# Wacky_Hat_Schematic.net
KiCad netlist of a schematic drawn in Altium Designer
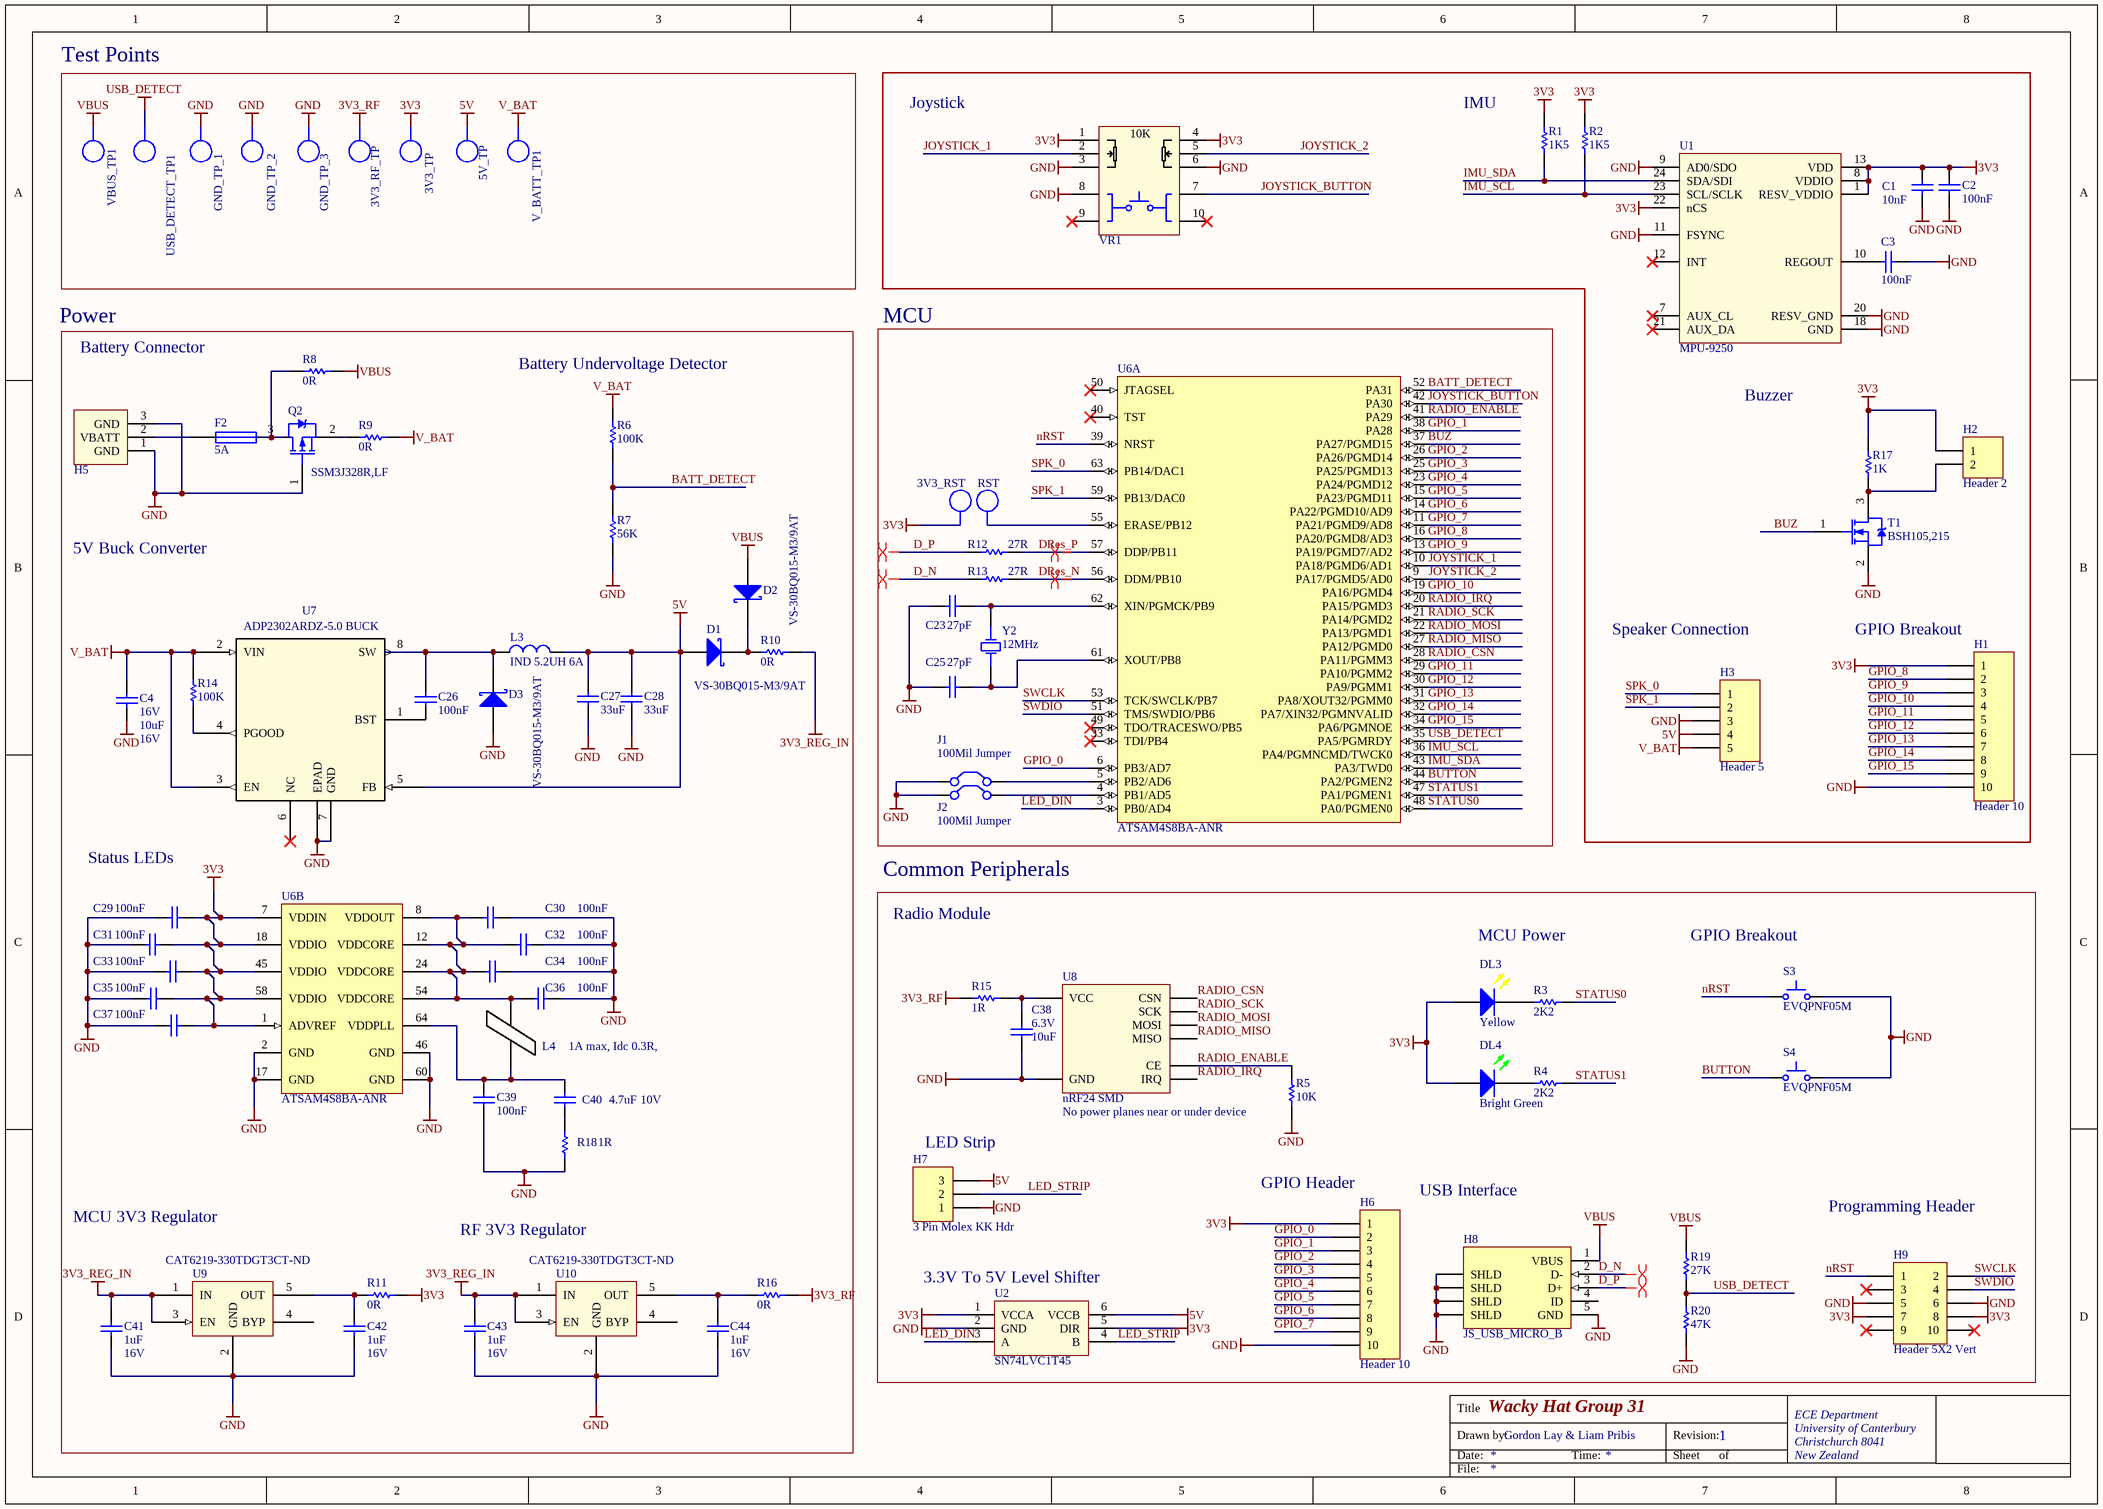
[diagram p0: Wacky Hat Schematic.SchDoc]

(export (version "E")
  (design (tool "Eeschema 10.0.6"))
  (components
    (comp (ref "3V3_RF_TP")
      (value "TP")
      (footprint "TP_1206")
      (description "Test-Point 3.3x1.6x2.1mm SMD")
      (fields
        (field (name "MANUFACTURER") "Harwin Inc")
        (field (name "MANUFACTURER PART NUMBER") "S1751-46R")
      )
      (libsource (lib "ECE AD19Components_19V1") (part "TP_1206"))
    )
    (comp (ref "3V3_RST")
      (value "TP")
      (footprint "TP_1206")
      (description "Test-Point 3.3x1.6x2.1mm SMD")
      (fields
        (field (name "MANUFACTURER") "Harwin Inc")
        (field (name "MANUFACTURER PART NUMBER") "S1751-46R")
      )
      (libsource (lib "ECE AD19Components_19V1") (part "TP_1206"))
    )
    (comp (ref "3V3_TP")
      (value "TP")
      (footprint "TP_1206")
      (description "Test-Point 3.3x1.6x2.1mm SMD")
      (fields
        (field (name "MANUFACTURER") "Harwin Inc")
        (field (name "MANUFACTURER PART NUMBER") "S1751-46R")
      )
      (libsource (lib "ECE AD19Components_19V1") (part "TP_1206"))
    )
    (comp (ref "5V_TP")
      (value "TP")
      (footprint "TP_1206")
      (description "Test-Point 3.3x1.6x2.1mm SMD")
      (fields
        (field (name "MANUFACTURER") "Harwin Inc")
        (field (name "MANUFACTURER PART NUMBER") "S1751-46R")
      )
      (libsource (lib "ECE AD19Components_19V1") (part "TP_1206"))
    )
    (comp (ref "C1")
      (value "10nF")
      (footprint "CAPC1608L")
      (description "CAP CER 10nF X7R +-10% 50V 0603")
      (libsource (lib "ECE AD19Components_19V1") (part "CC_10nF_0603"))
    )
    (comp (ref "C2")
      (value "100nF")
      (footprint "CAPC1608L")
      (description "CAP CER 100nF X7R +-10% 50V 0603")
      (libsource (lib "ECE AD19Components_19V1") (part "CC_100nF_0603"))
    )
    (comp (ref "C3")
      (value "100nF")
      (footprint "CAPC1608L")
      (description "CAP CER 100nF X7R +-10% 50V 0603")
      (libsource (lib "ECE AD19Components_19V1") (part "CC_100nF_0603"))
    )
    (comp (ref "C4")
      (value "10uF")
      (footprint "CAPC2012L")
      (description "CAP CER 10uF X5R 16V 0805")
      (fields
        (field (name "MANUFACTURER") "Samsung Electro-Mechanics")
        (field (name "MANUFACTURER PART NUMBER") "CL21A106KOQNNWE")
        (field (name "VOLTAGE - RATED") "16V")
        (field (name "MAX VOLTAGE") "16V")
      )
      (libsource (lib "ENCE461AD19_19V2") (part "CC_10uF_16V_0805"))
    )
    (comp (ref "C23")
      (value "27pF")
      (footprint "CAPC1608L")
      (description "CAP CER 27pF NPO/COG +-5% 50V 0603")
      (libsource (lib "ECE AD19Components_19V1") (part "CC_27pF_0603"))
    )
    (comp (ref "C25")
      (value "27pF")
      (footprint "CAPC1608L")
      (description "CAP CER 27pF NPO/COG +-5% 50V 0603")
      (libsource (lib "ECE AD19Components_19V1") (part "CC_27pF_0603"))
    )
    (comp (ref "C26")
      (value "100nF")
      (footprint "CAPC1608L")
      (description "CAP CER 100nF X7R +-10% 50V 0603")
      (libsource (lib "ECE AD19Components_19V1") (part "CC_100nF_0603"))
    )
    (comp (ref "C27")
      (value "33uF")
      (footprint "CAPC2012L")
      (description "CAP CER 33uF X5R 6V3 0805")
      (fields
        (field (name "MANUFACTURER") "TDK Corporation")
        (field (name "MANUFACTURER PART NUMBER") "C2012X5R0J336M125AC")
      )
      (libsource (lib "ENCE461AD19_19V2") (part "CC_33uF_6V3_0805"))
    )
    (comp (ref "C28")
      (value "33uF")
      (footprint "CAPC2012L")
      (description "CAP CER 33uF X5R 6V3 0805")
      (fields
        (field (name "MANUFACTURER") "TDK Corporation")
        (field (name "MANUFACTURER PART NUMBER") "C2012X5R0J336M125AC")
      )
      (libsource (lib "ENCE461AD19_19V2") (part "CC_33uF_6V3_0805"))
    )
    (comp (ref "C29")
      (value "100nF")
      (footprint "CAPC1608L")
      (description "CAP CER 100nF X7R +-10% 50V 0603")
      (libsource (lib "ECE AD19Components_19V1") (part "CC_100nF_0603"))
    )
    (comp (ref "C30")
      (value "100nF")
      (footprint "CAPC1608L")
      (description "CAP CER 100nF X7R +-10% 50V 0603")
      (libsource (lib "ECE AD19Components_19V1") (part "CC_100nF_0603"))
    )
    (comp (ref "C31")
      (value "100nF")
      (footprint "CAPC1608L")
      (description "CAP CER 100nF X7R +-10% 50V 0603")
      (libsource (lib "ECE AD19Components_19V1") (part "CC_100nF_0603"))
    )
    (comp (ref "C32")
      (value "100nF")
      (footprint "CAPC1608L")
      (description "CAP CER 100nF X7R +-10% 50V 0603")
      (libsource (lib "ECE AD19Components_19V1") (part "CC_100nF_0603"))
    )
    (comp (ref "C33")
      (value "100nF")
      (footprint "CAPC1608L")
      (description "CAP CER 100nF X7R +-10% 50V 0603")
      (libsource (lib "ECE AD19Components_19V1") (part "CC_100nF_0603"))
    )
    (comp (ref "C34")
      (value "100nF")
      (footprint "CAPC1608L")
      (description "CAP CER 100nF X7R +-10% 50V 0603")
      (libsource (lib "ECE AD19Components_19V1") (part "CC_100nF_0603"))
    )
    (comp (ref "C35")
      (value "100nF")
      (footprint "CAPC1608L")
      (description "CAP CER 100nF X7R +-10% 50V 0603")
      (libsource (lib "ECE AD19Components_19V1") (part "CC_100nF_0603"))
    )
    (comp (ref "C36")
      (value "100nF")
      (footprint "CAPC1608L")
      (description "CAP CER 100nF X7R +-10% 50V 0603")
      (libsource (lib "ECE AD19Components_19V1") (part "CC_100nF_0603"))
    )
    (comp (ref "C37")
      (value "100nF")
      (footprint "CAPC1608L")
      (description "CAP CER 100nF X7R +-10% 50V 0603")
      (libsource (lib "ECE AD19Components_19V1") (part "CC_100nF_0603"))
    )
    (comp (ref "C38")
      (value "10uF")
      (footprint "CAPC1608L")
      (description "CAP CER 10UF X5R +-20% 6V3 0603")
      (fields (field (name "VOLTAGE - RATED") "6.3V"))
      (libsource (lib "ECE AD19Components_19V1") (part "CC_10uF_0603"))
    )
    (comp (ref "C39")
      (value "100nF")
      (footprint "CAPC1608L")
      (description "CAP CER 100nF X7R +-10% 50V 0603")
      (libsource (lib "ECE AD19Components_19V1") (part "CC_100nF_0603"))
    )
    (comp (ref "C40")
      (value "4.7uF")
      (footprint "CAPC1608N")
      (description "CAP CER 4.7uF X5R +-20%  10V 0603")
      (fields (field (name "MAX VOLTAGE") "10V"))
      (libsource (lib "ECE AD19Components_19V1") (part "CC_4.7uF_0603"))
    )
    (comp (ref "C41")
      (value "1uF")
      (footprint "CAPC1608L")
      (description "CAP CER 1uF Y5V -20% +80% 16V 0603")
      (fields (field (name "MAX VOLTAGE") "16V"))
      (libsource (lib "ECE AD19Components_19V1") (part "CC_1uF_0603"))
    )
    (comp (ref "C42")
      (value "1uF")
      (footprint "CAPC1608L")
      (description "CAP CER 1uF Y5V -20% +80% 16V 0603")
      (fields (field (name "MAX VOLTAGE") "16V"))
      (libsource (lib "ECE AD19Components_19V1") (part "CC_1uF_0603"))
    )
    (comp (ref "C43")
      (value "1uF")
      (footprint "CAPC1608L")
      (description "CAP CER 1uF Y5V -20% +80% 16V 0603")
      (fields (field (name "MAX VOLTAGE") "16V"))
      (libsource (lib "ECE AD19Components_19V1") (part "CC_1uF_0603"))
    )
    (comp (ref "C44")
      (value "1uF")
      (footprint "CAPC1608L")
      (description "CAP CER 1uF Y5V -20% +80% 16V 0603")
      (fields (field (name "MAX VOLTAGE") "16V"))
      (libsource (lib "ECE AD19Components_19V1") (part "CC_1uF_0603"))
    )
    (comp (ref "D1")
      (value "VS-30BQ015-M3/9AT")
      (footprint "SMC")
      (description "DIODE, SCHOTTKY, 3A, 15V, DO-214AB / SMC")
      (fields (field (name "MANUFACTURER") "Vishay Semiconductors"))
      (libsource (lib "ECE AD19Components_19V1") (part "DS_VS-30BQ015-M3"))
    )
    (comp (ref "D2")
      (value "VS-30BQ015-M3/9AT")
      (footprint "SMC")
      (description "DIODE, SCHOTTKY, 3A, 15V, DO-214AB / SMC")
      (fields (field (name "MANUFACTURER") "Vishay Semiconductors"))
      (libsource (lib "ECE AD19Components_19V1") (part "DS_VS-30BQ015-M3"))
    )
    (comp (ref "D3")
      (value "VS-30BQ015-M3/9AT")
      (footprint "SMC")
      (description "DIODE, SCHOTTKY, 3A, 15V, DO-214AB / SMC")
      (fields (field (name "MANUFACTURER") "Vishay Semiconductors"))
      (libsource (lib "ECE AD19Components_19V1") (part "DS_VS-30BQ015-M3"))
    )
    (comp (ref "DL3")
      (value "Yellow")
      (footprint "WL-SMCW0603")
      (description "LED Yellow 120mcd 0603 SMD")
      (fields
        (field (name "MANUFACTURER") "WURTH ELEKTRONIK")
        (field (name "MANUFACTURER PART NUMBER") "150060YS75000")
        (field (name "LED COLOUR") "Yellow")
      )
      (libsource (lib "ECE AD19Components_19V1") (part "DL_150060YS75000"))
    )
    (comp (ref "DL4")
      (value "Bright Green")
      (footprint "WL-SMCW0603")
      (description "LED Bright Green 40mcd 0603 SMD")
      (fields
        (field (name "MANUFACTURER") "WURTH ELEKTRONIK")
        (field (name "MANUFACTURER PART NUMBER") "150060VS75000")
        (field (name "LED COLOUR") "Bright Green")
      )
      (libsource (lib "ECE AD19Components_19V1") (part "DL_150060VS75000"))
    )
    (comp (ref "F2")
      (value "5A")
      (footprint "RESC3216N")
      (description "Fuse 5.0A Fast Acting 1206 SMD")
      (fields (field (name "MANUFACTURER PART NUMBER") "C1F5") (field (name "MANUFACTURER") "Bel TRP"))
      (libsource (lib "ECE AD19Components_19V1") (part "FS_Fuse_5.0A"))
    )
    (comp (ref "GND_TP_1")
      (value "TP")
      (footprint "TP_1206")
      (description "Test-Point 3.3x1.6x2.1mm SMD")
      (fields
        (field (name "MANUFACTURER") "Harwin Inc")
        (field (name "MANUFACTURER PART NUMBER") "S1751-46R")
      )
      (libsource (lib "ECE AD19Components_19V1") (part "TP_1206"))
    )
    (comp (ref "GND_TP_2")
      (value "TP")
      (footprint "TP_1206")
      (description "Test-Point 3.3x1.6x2.1mm SMD")
      (fields
        (field (name "MANUFACTURER") "Harwin Inc")
        (field (name "MANUFACTURER PART NUMBER") "S1751-46R")
      )
      (libsource (lib "ECE AD19Components_19V1") (part "TP_1206"))
    )
    (comp (ref "GND_TP_3")
      (value "TP")
      (footprint "TP_1206")
      (description "Test-Point 3.3x1.6x2.1mm SMD")
      (fields
        (field (name "MANUFACTURER") "Harwin Inc")
        (field (name "MANUFACTURER PART NUMBER") "S1751-46R")
      )
      (libsource (lib "ECE AD19Components_19V1") (part "TP_1206"))
    )
    (comp (ref "H1")
      (value "Header 10")
      (footprint "HDR1X10")
      (description "Header, 10-Pin")
      (fields (field (name "PUBLISHER") "Altium Limited"))
      (libsource (lib "Miscellaneous Connectors") (part "Header 10"))
    )
    (comp (ref "H2")
      (value "Header 2")
      (footprint "HDR1X2")
      (description "Header, 2-Pin")
      (fields (field (name "PUBLISHER") "Altium Limited"))
      (libsource (lib "Miscellaneous Connectors") (part "Header 2"))
    )
    (comp (ref "H3")
      (value "Header 5")
      (footprint "HDR1X5")
      (description "Header, 5-Pin")
      (fields (field (name "PUBLISHER") "Altium Limited"))
      (libsource (lib "Miscellaneous Connectors") (part "Header 5"))
    )
    (comp (ref "H5")
      (value "Battery_HEADER_3pin")
      (footprint "BATT_HEADER_3POS")
      (description "3Pin Header 2.54mm spacing")
      (libsource (lib "ENCE461AD19_19V2") (part "Battery_HEADER_3pin"))
    )
    (comp (ref "H6")
      (value "Header 10")
      (footprint "HDR1X10")
      (description "Header, 10-Pin")
      (fields (field (name "PUBLISHER") "Altium Limited"))
      (libsource (lib "Miscellaneous Connectors") (part "Header 10"))
    )
    (comp (ref "H7")
      (value "3 Pin Molex KK Hdr")
      (footprint "MOLEX_KK_3_HDR")
      (description "CONN HEADER 3POS 2.54mm VERT_Thru Hole")
      (fields (field (name "MANUFACTURER") "Molex"))
      (libsource (lib "ECE AD19Components_19V1") (part "JA_MOLEX_KK_3POS"))
    )
    (comp (ref "H8")
      (value "JS_USB_MICRO_B")
      (footprint "FCI_USB_10118194-0001LF")
      (description "CONN USB MICRO B RECPT SMT R/A")
      (fields (field (name "MANUFACTURER") "FCI") (field (name "MANUFACTURER PART NUMBER") "10118194-0001LF"))
      (libsource (lib "ECE AD19Components_19V1") (part "JS_USB_MICRO_B_SMT"))
    )
    (comp (ref "H9")
      (value "Header 5X2 Vert")
      (footprint "IDC2.54-V10D")
      (description "IDC Header, 2,54mm, 10-Pin, Vert")
      (libsource (lib "ECE AD19Components_19V1") (part "JA_HDR_IDC_5X2_VERT"))
    )
    (comp (ref "J1")
      (value "100Mil Jumper")
      (footprint "JMP2.54")
      (description "2.54mm Jumper Thru Hole")
      (libsource (lib "ECE AD19Components_19V1") (part "TP_JUMPER"))
    )
    (comp (ref "J2")
      (value "100Mil Jumper")
      (footprint "JMP2.54")
      (description "2.54mm Jumper Thru Hole")
      (libsource (lib "ECE AD19Components_19V1") (part "TP_JUMPER"))
    )
    (comp (ref "L3")
      (value "IND 5.2UH 6A")
      (footprint "INDUCTOR5u2")
      (description "FIXED IND 5.2UH 6A 22 MOHM SMD")
      (fields
        (field (name "MANUFACTURER") "Sumida America Components Inc.")
        (field (name "MANUFACTURER PART NUMBER") "CDRH104RNP-5R2NC")
      )
      (libsource (lib "ENCE461AD19_19V2") (part "CDRH104RNP-5R2NC"))
    )
    (comp (ref "L4")
      (value "1A max, Idc 0.3R,")
      (footprint "INDC3216L")
      (description "Ferrite Bead, Rdc 0.3R, Z100MHZ 600R, Imax 1A, SMD 1206")
      (fields
        (field (name "MANUFACTURER") "FAIR-RITE")
        (field (name "MANUFACTURER PART NUMBER") "2512066017Y1")
      )
      (libsource (lib "ECE AD19Components_19V1") (part "IN_Ferrite-Bead"))
    )
    (comp (ref "Q2")
      (value "SSM3J328R,LF")
      (footprint "SOT23_L")
      (description "MOSFET P-CH 20V 6A SOT23-3")
      (fields
        (field (name "MANUFACTURER") "Toshiba")
        (field (name "MANUFACTURER PART NUMBER") "SSM3J328R,LF")
      )
      (libsource (lib "ECE AD19Components_19V1") (part "TM_SSM3J328R"))
    )
    (comp (ref "R1")
      (value "1K5")
      (footprint "RESC1608L")
      (description "RES 1.5K OHM 1/10W 5% 0603 SMD")
      (libsource (lib "ECE AD19Components_19V1") (part "RS_1K5"))
    )
    (comp (ref "R2")
      (value "1K5")
      (footprint "RESC1608L")
      (description "RES 1.5K OHM 1/10W 5% 0603 SMD")
      (libsource (lib "ECE AD19Components_19V1") (part "RS_1K5"))
    )
    (comp (ref "R3")
      (value "2K2")
      (footprint "RESC1608L")
      (description "RES 2.2K OHM 1/10W 5% 0603 SMD")
      (libsource (lib "ECE AD19Components_19V1") (part "RS_2K2"))
    )
    (comp (ref "R4")
      (value "2K2")
      (footprint "RESC1608L")
      (description "RES 2.2K OHM 1/10W 5% 0603 SMD")
      (libsource (lib "ECE AD19Components_19V1") (part "RS_2K2"))
    )
    (comp (ref "R5")
      (value "10K")
      (footprint "RESC1608L")
      (description "RES 10.0K OHM 1/10W 5% 0603 SMD")
      (libsource (lib "ECE AD19Components_19V1") (part "RS_10K"))
    )
    (comp (ref "R6")
      (value "100K")
      (footprint "RESC1608L")
      (description "RES 100K OHM 1/10W 5% 0603 SMD")
      (libsource (lib "ECE AD19Components_19V1") (part "RS_100K"))
    )
    (comp (ref "R7")
      (value "56K")
      (footprint "RESC1608L")
      (description "RES 56.0K OHM 1/10W 5% 0603 SMD")
      (libsource (lib "ECE AD19Components_19V1") (part "RS_56K"))
    )
    (comp (ref "R8")
      (value "0R")
      (footprint "RESC1608L")
      (description "RES 0.0 OHM 1/10W 5% 0603 SMD")
      (libsource (lib "ECE AD19Components_19V1") (part "RS_0R0"))
    )
    (comp (ref "R9")
      (value "0R")
      (footprint "RESC1608L")
      (description "RES 0.0 OHM 1/10W 5% 0603 SMD")
      (libsource (lib "ECE AD19Components_19V1") (part "RS_0R0"))
    )
    (comp (ref "R10")
      (value "0R")
      (footprint "RESC1608L")
      (description "RES 0.0 OHM 1/10W 5% 0603 SMD")
      (libsource (lib "ECE AD19Components_19V1") (part "RS_0R0"))
    )
    (comp (ref "R11")
      (value "0R")
      (footprint "RESC1608L")
      (description "RES 0.0 OHM 1/10W 5% 0603 SMD")
      (libsource (lib "ECE AD19Components_19V1") (part "RS_0R0"))
    )
    (comp (ref "R12")
      (value "27R")
      (footprint "RESC1608L")
      (description "RES 27 OHM 1/10W 5% 0603 SMD")
      (libsource (lib "ECE AD19Components_19V1") (part "RS_27R"))
    )
    (comp (ref "R13")
      (value "27R")
      (footprint "RESC1608L")
      (description "RES 27 OHM 1/10W 5% 0603 SMD")
      (libsource (lib "ECE AD19Components_19V1") (part "RS_27R"))
    )
    (comp (ref "R14")
      (value "100K")
      (footprint "RESC1608L")
      (description "RES 100K OHM 1/10W 5% 0603 SMD")
      (libsource (lib "ECE AD19Components_19V1") (part "RS_100K"))
    )
    (comp (ref "R15")
      (value "1R")
      (footprint "RESC3216L")
      (description "RES 1R OHM 1/4W 5% 1206 SMD")
      (libsource (lib "ECE AD19Components_19V1") (part "RT_1R"))
    )
    (comp (ref "R16")
      (value "0R")
      (footprint "RESC1608L")
      (description "RES 0.0 OHM 1/10W 5% 0603 SMD")
      (libsource (lib "ECE AD19Components_19V1") (part "RS_0R0"))
    )
    (comp (ref "R17")
      (value "1K")
      (footprint "RESC1608L")
      (description "RES 1.0K OHM 1/10W 5% 0603 SMD")
      (libsource (lib "ECE AD19Components_19V1") (part "RS_1K"))
    )
    (comp (ref "R18")
      (value "1R")
      (footprint "RESC3216L")
      (description "RES 1R OHM 1/4W 5% 1206 SMD")
      (libsource (lib "ECE AD19Components_19V1") (part "RT_1R"))
    )
    (comp (ref "R19")
      (value "27K")
      (footprint "RESC1608L")
      (description "RES 27K OHM 1/10W 5% 0603 SMD")
      (libsource (lib "ECE AD19Components_19V1") (part "RS_27K"))
    )
    (comp (ref "R20")
      (value "47K")
      (footprint "RESC1608L")
      (description "RES 47.0K OHM 1/10W 5% 0603 SMD")
      (libsource (lib "ECE AD19Components_19V1") (part "RS_47K"))
    )
    (comp (ref "RST")
      (value "TP")
      (footprint "TP_1206")
      (description "Test-Point 3.3x1.6x2.1mm SMD")
      (fields
        (field (name "MANUFACTURER") "Harwin Inc")
        (field (name "MANUFACTURER PART NUMBER") "S1751-46R")
      )
      (libsource (lib "ECE AD19Components_19V1") (part "TP_1206"))
    )
    (comp (ref "S3")
      (value "EVQPNF05M")
      (footprint "EVQPNF05M")
      (description "Panasonic 6 x 3.5mm SMD Light Touch Switch Type SMD")
      (fields (field (name "MANUFACTURER") "Panasonic"))
      (libsource (lib "ECE AD19Components_19V1") (part "WS_EVQPNF05M"))
    )
    (comp (ref "S4")
      (value "EVQPNF05M")
      (footprint "EVQPNF05M")
      (description "Panasonic 6 x 3.5mm SMD Light Touch Switch Type SMD")
      (fields (field (name "MANUFACTURER") "Panasonic"))
      (libsource (lib "ECE AD19Components_19V1") (part "WS_EVQPNF05M"))
    )
    (comp (ref "T1")
      (value "BSH105,215")
      (footprint "SOT23_L")
      (description "MOSFET N-CH 20V 1.05A SOT-23")
      (fields
        (field (name "MANUFACTURER") "NXP Semiconductors")
        (field (name "MANUFACTURER PART NUMBER") "BSH105,215")
      )
      (libsource (lib "ECE AD19Components_19V1") (part "TM_BSH105"))
    )
    (comp (ref "U1")
      (value "MPU-9250")
      (footprint "Quad24")
      (description "9 axis IMU")
      (libsource (lib "ENCE461AD19_19V2") (part "MPU-9250"))
    )
    (comp (ref "U2")
      (value "SN74LVC1T45")
      (footprint "SOT23-6_N")
      (description "1.8V - 5V level converter")
      (libsource (lib "ENCE461_extras_2020") (part "SN74LVC1T45"))
    )
    (comp (ref "U6")
      (value "ATSAM4S8BA-ANR")
      (footprint "LQFP64_L")
      (description "IC MCU 32BIT 512KB FLASH 64LQFP")
      (fields (field (name "MANUFACTURER") "Atmel"))
      (libsource (lib "ECE AD19Components_19V1") (part "SE_ATSAM4S16BA-MU"))
    )
    (comp (ref "U7")
      (value "ADP2302ARDZ-5.0 BUCK")
      (footprint "RD_8_1")
      (description "IC REG BUCK 5V 2A 8SOIC")
      (fields (field (name "MANUFACTURER_PART_NUMBER") "ADP2302ARDZ-5.0-R7"))
      (libsource (lib "ENCE461AD19_19V2") (part "ADP2302ARDZ-5.0-R7"))
    )
    (comp (ref "U8")
      (value "nRF24 SMD")
      (footprint "NRF24")
      (description "nRF24 SMD Module")
      (fields (field (name "WARNING") "No power planes near or under device"))
      (libsource (lib "ENCE461AD19_19V2") (part "NRF24"))
    )
    (comp (ref "U9")
      (value "CAT6219-330TDGT3")
      (footprint "SOT95P280X145-5N")
      (description "IC REG LIN 3.3V 500MA TSOT23-5")
      (fields
        (field (name "BASE PART NUMBER") "CAT6219")
        (field (name "SUPPLIER PART NUMBER") "CAT6219-330TDGT3CT-ND")
      )
      (libsource (lib "ENCE461AD19_19V2") (part "SV_CAT6219-330TDGT3"))
    )
    (comp (ref "U10")
      (value "CAT6219-330TDGT3")
      (footprint "SOT95P280X145-5N")
      (description "IC REG LIN 3.3V 500MA TSOT23-5")
      (fields
        (field (name "BASE PART NUMBER") "CAT6219")
        (field (name "SUPPLIER PART NUMBER") "CAT6219-330TDGT3CT-ND")
      )
      (libsource (lib "ENCE461AD19_19V2") (part "SV_CAT6219-330TDGT3"))
    )
    (comp (ref "USB_DETECT_TP1")
      (value "TP")
      (footprint "TP_1206")
      (description "Test-Point 3.3x1.6x2.1mm SMD")
      (fields
        (field (name "MANUFACTURER") "Harwin Inc")
        (field (name "MANUFACTURER PART NUMBER") "S1751-46R")
      )
      (libsource (lib "ECE AD19Components_19V1") (part "TP_1206"))
    )
    (comp (ref "VBUS_TP1")
      (value "TP")
      (footprint "TP_1206")
      (description "Test-Point 3.3x1.6x2.1mm SMD")
      (fields
        (field (name "MANUFACTURER") "Harwin Inc")
        (field (name "MANUFACTURER PART NUMBER") "S1751-46R")
      )
      (libsource (lib "ECE AD19Components_19V1") (part "TP_1206"))
    )
    (comp (ref "VR1")
      (value "Joystick 10k with Sw")
      (footprint "Joystick_Sw")
      (description "JOYSTICK 10K OHM 2 AXIS TH")
      (libsource (lib "ENCE461AD19_19V2") (part "Joystick 10k with Sw"))
    )
    (comp (ref "V_BATT_TP1")
      (value "TP")
      (footprint "TP_1206")
      (description "Test-Point 3.3x1.6x2.1mm SMD")
      (fields
        (field (name "MANUFACTURER") "Harwin Inc")
        (field (name "MANUFACTURER PART NUMBER") "S1751-46R")
      )
      (libsource (lib "ECE AD19Components_19V1") (part "TP_1206"))
    )
    (comp (ref "Y2")
      (value "12MHz")
      (footprint "6.0X3.5-4")
      (description "CRYSTAL 12MHZ 18PF 6X3.5mm SMD")
      (fields
        (field (name "MANUFACTURER") "CTS-Frequency Controls")
        (field (name "MANUFACTURER PART NUMBER") "406C35D12M00000")
        (field (name "FREQUENCY") "12MHz")
      )
      (libsource (lib "ECE AD19Components_19V1") (part "XT_CRYSTAL_12MHz_18pF"))
    )
  )
  (nets
    (net (code "1") (name "/BATT_DETECT") (class "Default")
      (node (ref "R6") (pin "1") (pinfunction "1_1") (pintype "passive"))
      (node (ref "R7") (pin "2") (pinfunction "2_2") (pintype "passive"))
      (node (ref "U6") (pin "52") (pinfunction "PA31_52") (pintype "bidirectional"))
    )
    (net (code "2") (name "/BUTTON") (class "Default")
      (node (ref "S4") (pin "1") (pintype "passive"))
      (node (ref "U6") (pin "44") (pinfunction "PA2/PGMEN2_44") (pintype "bidirectional"))
    )
    (net (code "3") (name "/BUZ") (class "Default")
      (node (ref "T1") (pin "1") (pinfunction "1_1") (pintype "passive"))
      (node (ref "U6") (pin "37") (pinfunction "PA27/PGMD15_37") (pintype "bidirectional"))
    )
    (net (code "4") (name "/DRes_N") (class "Default")
      (node (ref "R13") (pin "2") (pinfunction "2_2") (pintype "passive"))
      (node (ref "U6") (pin "56") (pinfunction "DDM/PB10_56") (pintype "bidirectional"))
    )
    (net (code "5") (name "/DRes_P") (class "Default")
      (node (ref "R12") (pin "2") (pinfunction "2_2") (pintype "passive"))
      (node (ref "U6") (pin "57") (pinfunction "DDP/PB11_57") (pintype "bidirectional"))
    )
    (net (code "6") (name "/D_N") (class "Default")
      (node (ref "H8") (pin "2") (pinfunction "D-_2") (pintype "input"))
      (node (ref "R13") (pin "1") (pinfunction "1_1") (pintype "passive"))
    )
    (net (code "7") (name "/D_P") (class "Default")
      (node (ref "H8") (pin "3") (pinfunction "D+_3") (pintype "input"))
      (node (ref "R12") (pin "1") (pinfunction "1_1") (pintype "passive"))
    )
    (net (code "8") (name "/GPIO_0") (class "Default")
      (node (ref "H6") (pin "2") (pinfunction "2_2") (pintype "passive"))
      (node (ref "U6") (pin "6") (pinfunction "PB3/AD7_6") (pintype "bidirectional"))
    )
    (net (code "9") (name "/GPIO_1") (class "Default")
      (node (ref "H6") (pin "3") (pinfunction "3_3") (pintype "passive"))
      (node (ref "U6") (pin "38") (pinfunction "PA28_38") (pintype "bidirectional"))
    )
    (net (code "10") (name "/GPIO_2") (class "Default")
      (node (ref "H6") (pin "4") (pinfunction "4_4") (pintype "passive"))
      (node (ref "U6") (pin "26") (pinfunction "PA26/PGMD14_26") (pintype "bidirectional"))
    )
    (net (code "11") (name "/GPIO_3") (class "Default")
      (node (ref "H6") (pin "5") (pinfunction "5_5") (pintype "passive"))
      (node (ref "U6") (pin "25") (pinfunction "PA25/PGMD13_25") (pintype "bidirectional"))
    )
    (net (code "12") (name "/GPIO_4") (class "Default")
      (node (ref "H6") (pin "6") (pinfunction "6_6") (pintype "passive"))
      (node (ref "U6") (pin "23") (pinfunction "PA24/PGMD12_23") (pintype "bidirectional"))
    )
    (net (code "13") (name "/GPIO_5") (class "Default")
      (node (ref "H6") (pin "7") (pinfunction "7_7") (pintype "passive"))
      (node (ref "U6") (pin "15") (pinfunction "PA23/PGMD11_15") (pintype "bidirectional"))
    )
    (net (code "14") (name "/GPIO_6") (class "Default")
      (node (ref "H6") (pin "8") (pinfunction "8_8") (pintype "passive"))
      (node (ref "U6") (pin "14") (pinfunction "PA22/PGMD10/AD9_14") (pintype "bidirectional"))
    )
    (net (code "15") (name "/GPIO_7") (class "Default")
      (node (ref "H6") (pin "9") (pinfunction "9_9") (pintype "passive"))
      (node (ref "U6") (pin "11") (pinfunction "PA21/PGMD9/AD8_11") (pintype "bidirectional"))
    )
    (net (code "16") (name "/GPIO_8") (class "Default")
      (node (ref "H1") (pin "2") (pinfunction "2_2") (pintype "passive"))
      (node (ref "U6") (pin "16") (pinfunction "PA20/PGMD8/AD3_16") (pintype "bidirectional"))
    )
    (net (code "17") (name "/GPIO_9") (class "Default")
      (node (ref "H1") (pin "3") (pinfunction "3_3") (pintype "passive"))
      (node (ref "U6") (pin "13") (pinfunction "PA19/PGMD7/AD2_13") (pintype "bidirectional"))
    )
    (net (code "18") (name "/GPIO_10") (class "Default")
      (node (ref "H1") (pin "4") (pinfunction "4_4") (pintype "passive"))
      (node (ref "U6") (pin "19") (pinfunction "PA16/PGMD4_19") (pintype "bidirectional"))
    )
    (net (code "19") (name "/GPIO_11") (class "Default")
      (node (ref "H1") (pin "5") (pinfunction "5_5") (pintype "passive"))
      (node (ref "U6") (pin "29") (pinfunction "PA10/PGMM2_29") (pintype "bidirectional"))
    )
    (net (code "20") (name "/GPIO_12") (class "Default")
      (node (ref "H1") (pin "6") (pinfunction "6_6") (pintype "passive"))
      (node (ref "U6") (pin "30") (pinfunction "PA9/PGMM1_30") (pintype "bidirectional"))
    )
    (net (code "21") (name "/GPIO_13") (class "Default")
      (node (ref "H1") (pin "7") (pinfunction "7_7") (pintype "passive"))
      (node (ref "U6") (pin "31") (pinfunction "PA8/XOUT32/PGMM0_31") (pintype "bidirectional"))
    )
    (net (code "22") (name "/GPIO_14") (class "Default")
      (node (ref "H1") (pin "8") (pinfunction "8_8") (pintype "passive"))
      (node (ref "U6") (pin "32") (pinfunction "PA7/XIN32/PGMNVALID_32") (pintype "bidirectional"))
    )
    (net (code "23") (name "/GPIO_15") (class "Default")
      (node (ref "H1") (pin "9") (pinfunction "9_9") (pintype "passive"))
      (node (ref "U6") (pin "34") (pinfunction "PA6/PGMNOE_34") (pintype "bidirectional"))
    )
    (net (code "24") (name "/IMU_SCL") (class "Default")
      (node (ref "R2") (pin "1") (pinfunction "1_1") (pintype "passive"))
      (node (ref "U1") (pin "23") (pinfunction "SCL/SCLK_23") (pintype "passive"))
      (node (ref "U6") (pin "36") (pinfunction "PA4/PGMNCMD/TWCK0_36") (pintype "bidirectional"))
    )
    (net (code "25") (name "/IMU_SDA") (class "Default")
      (node (ref "R1") (pin "1") (pinfunction "1_1") (pintype "passive"))
      (node (ref "U1") (pin "24") (pinfunction "SDA/SDI_24") (pintype "passive"))
      (node (ref "U6") (pin "43") (pinfunction "PA3/TWD0_43") (pintype "bidirectional"))
    )
    (net (code "26") (name "/JOYSTICK_1") (class "Default")
      (node (ref "U6") (pin "10") (pinfunction "PA18/PGMD6/AD1_10") (pintype "bidirectional"))
      (node (ref "VR1") (pin "2") (pinfunction "2_2") (pintype "passive"))
    )
    (net (code "27") (name "/JOYSTICK_2") (class "Default")
      (node (ref "U6") (pin "9") (pinfunction "PA17/PGMD5/AD0_9") (pintype "bidirectional"))
      (node (ref "VR1") (pin "5") (pinfunction "2'_5") (pintype "passive"))
    )
    (net (code "28") (name "/JOYSTICK_BUTTON") (class "Default")
      (node (ref "U6") (pin "42") (pinfunction "PA30_42") (pintype "bidirectional"))
      (node (ref "VR1") (pin "7") (pinfunction "7_7") (pintype "passive"))
    )
    (net (code "29") (name "/LED_DIN") (class "Default")
      (node (ref "U2") (pin "3") (pinfunction "A_3") (pintype "passive"))
      (node (ref "U6") (pin "3") (pinfunction "PB0/AD4_3") (pintype "bidirectional"))
    )
    (net (code "30") (name "/LED_STRIP") (class "Default")
      (node (ref "H7") (pin "2") (pinfunction "2_2") (pintype "passive"))
      (node (ref "U2") (pin "4") (pinfunction "B_4") (pintype "passive"))
    )
    (net (code "31") (name "/RADIO_CSN") (class "Default")
      (node (ref "U6") (pin "28") (pinfunction "PA11/PGMM3_28") (pintype "bidirectional"))
      (node (ref "U8") (pin "4") (pinfunction "CSN_4") (pintype "passive"))
    )
    (net (code "32") (name "/RADIO_ENABLE") (class "Default")
      (node (ref "R5") (pin "2") (pinfunction "2_2") (pintype "passive"))
      (node (ref "U6") (pin "41") (pinfunction "PA29_41") (pintype "bidirectional"))
      (node (ref "U8") (pin "3") (pinfunction "CE_3") (pintype "passive"))
    )
    (net (code "33") (name "/RADIO_IRQ") (class "Default")
      (node (ref "U6") (pin "20") (pinfunction "PA15/PGMD3_20") (pintype "bidirectional"))
      (node (ref "U8") (pin "8") (pinfunction "IRQ_8") (pintype "passive"))
    )
    (net (code "34") (name "/RADIO_MISO") (class "Default")
      (node (ref "U6") (pin "27") (pinfunction "PA12/PGMD0_27") (pintype "bidirectional"))
      (node (ref "U8") (pin "7") (pinfunction "MISO_7") (pintype "passive"))
    )
    (net (code "35") (name "/RADIO_MOSI") (class "Default")
      (node (ref "U6") (pin "22") (pinfunction "PA13/PGMD1_22") (pintype "bidirectional"))
      (node (ref "U8") (pin "6") (pinfunction "MOSI_6") (pintype "passive"))
    )
    (net (code "36") (name "/RADIO_SCK") (class "Default")
      (node (ref "U6") (pin "21") (pinfunction "PA14/PGMD2_21") (pintype "bidirectional"))
      (node (ref "U8") (pin "5") (pinfunction "SCK_5") (pintype "passive"))
    )
    (net (code "37") (name "/SPK_0") (class "Default")
      (node (ref "H3") (pin "1") (pinfunction "1_1") (pintype "passive"))
      (node (ref "U6") (pin "63") (pinfunction "PB14/DAC1_63") (pintype "bidirectional"))
    )
    (net (code "38") (name "/SPK_1") (class "Default")
      (node (ref "H3") (pin "2") (pinfunction "2_2") (pintype "passive"))
      (node (ref "U6") (pin "59") (pinfunction "PB13/DAC0_59") (pintype "bidirectional"))
    )
    (net (code "39") (name "/STATUS0") (class "Default")
      (node (ref "R3") (pin "2") (pinfunction "2_2") (pintype "passive"))
      (node (ref "U6") (pin "48") (pinfunction "PA0/PGMEN0_48") (pintype "bidirectional"))
    )
    (net (code "40") (name "/STATUS1") (class "Default")
      (node (ref "R4") (pin "2") (pinfunction "2_2") (pintype "passive"))
      (node (ref "U6") (pin "47") (pinfunction "PA1/PGMEN1_47") (pintype "bidirectional"))
    )
    (net (code "41") (name "/SWCLK") (class "Default")
      (node (ref "H9") (pin "2") (pinfunction "2_2") (pintype "passive"))
      (node (ref "U6") (pin "53") (pinfunction "TCK/SWCLK/PB7_53") (pintype "bidirectional"))
    )
    (net (code "42") (name "/SWDIO") (class "Default")
      (node (ref "H9") (pin "4") (pinfunction "4_4") (pintype "passive"))
      (node (ref "U6") (pin "51") (pinfunction "TMS/SWDIO/PB6_51") (pintype "bidirectional"))
    )
    (net (code "43") (name "/nRST") (class "Default")
      (node (ref "H9") (pin "1") (pinfunction "1_1") (pintype "passive"))
      (node (ref "S3") (pin "1") (pintype "passive"))
      (node (ref "U6") (pin "39") (pinfunction "NRST_39") (pintype "bidirectional"))
    )
    (net (code "44") (name "3V3") (class "Default")
      (node (ref "3V3_RST") (pin "1") (pinfunction "1_1") (pintype "passive"))
      (node (ref "3V3_TP") (pin "1") (pinfunction "1_1") (pintype "passive"))
      (node (ref "C1") (pin "2") (pinfunction "2_2") (pintype "passive"))
      (node (ref "C2") (pin "2") (pinfunction "2_2") (pintype "passive"))
      (node (ref "C29") (pin "2") (pinfunction "2_2") (pintype "passive"))
      (node (ref "C31") (pin "2") (pinfunction "2_2") (pintype "passive"))
      (node (ref "C33") (pin "2") (pinfunction "2_2") (pintype "passive"))
      (node (ref "C35") (pin "2") (pinfunction "2_2") (pintype "passive"))
      (node (ref "C37") (pin "2") (pinfunction "2_2") (pintype "passive"))
      (node (ref "DL3") (pin "2") (pinfunction "A_2") (pintype "passive"))
      (node (ref "DL4") (pin "2") (pinfunction "A_2") (pintype "passive"))
      (node (ref "H1") (pin "1") (pinfunction "1_1") (pintype "passive"))
      (node (ref "H2") (pin "1") (pinfunction "1_1") (pintype "passive"))
      (node (ref "H6") (pin "1") (pinfunction "1_1") (pintype "passive"))
      (node (ref "H9") (pin "7") (pinfunction "7_7") (pintype "passive"))
      (node (ref "H9") (pin "8") (pinfunction "8_8") (pintype "passive"))
      (node (ref "R1") (pin "2") (pinfunction "2_2") (pintype "passive"))
      (node (ref "R11") (pin "2") (pinfunction "2_2") (pintype "passive"))
      (node (ref "R17") (pin "2") (pinfunction "2_2") (pintype "passive"))
      (node (ref "R2") (pin "2") (pinfunction "2_2") (pintype "passive"))
      (node (ref "U1") (pin "1") (pinfunction "RESV_VDDIO_1") (pintype "passive"))
      (node (ref "U1") (pin "13") (pinfunction "VDD_13") (pintype "passive"))
      (node (ref "U1") (pin "22") (pinfunction "nCS_22") (pintype "passive"))
      (node (ref "U1") (pin "8") (pinfunction "VDDIO_8") (pintype "passive"))
      (node (ref "U2") (pin "1") (pinfunction "VCCA_1") (pintype "passive"))
      (node (ref "U2") (pin "5") (pinfunction "DIR_5") (pintype "passive"))
      (node (ref "U6") (pin "1") (pinfunction "ADVREF_1") (pintype "input"))
      (node (ref "U6") (pin "18") (pinfunction "VDDIO_18") (pintype "power_in"))
      (node (ref "U6") (pin "45") (pinfunction "VDDIO_45") (pintype "power_in"))
      (node (ref "U6") (pin "58") (pinfunction "VDDIO_58") (pintype "power_in"))
      (node (ref "U6") (pin "7") (pinfunction "VDDIN_7") (pintype "power_in"))
      (node (ref "VR1") (pin "1") (pinfunction "1_1") (pintype "passive"))
      (node (ref "VR1") (pin "4") (pinfunction "1'_4") (pintype "passive"))
    )
    (net (code "45") (name "3V3_REG_IN") (class "Default")
      (node (ref "C41") (pin "2") (pinfunction "2_2") (pintype "passive"))
      (node (ref "C43") (pin "2") (pinfunction "2_2") (pintype "passive"))
      (node (ref "R10") (pin "2") (pinfunction "2_2") (pintype "passive"))
      (node (ref "U10") (pin "1") (pinfunction "IN_1") (pintype "power_in"))
      (node (ref "U10") (pin "3") (pinfunction "EN_3") (pintype "input"))
      (node (ref "U9") (pin "1") (pinfunction "IN_1") (pintype "power_in"))
      (node (ref "U9") (pin "3") (pinfunction "EN_3") (pintype "input"))
    )
    (net (code "46") (name "3V3_RF") (class "Default")
      (node (ref "3V3_RF_TP") (pin "1") (pinfunction "1_1") (pintype "passive"))
      (node (ref "R15") (pin "1") (pinfunction "1_1") (pintype "passive"))
      (node (ref "R16") (pin "2") (pinfunction "2_2") (pintype "passive"))
    )
    (net (code "47") (name "5V") (class "Default")
      (node (ref "5V_TP") (pin "1") (pinfunction "1_1") (pintype "passive"))
      (node (ref "C27") (pin "2") (pinfunction "2_2") (pintype "passive"))
      (node (ref "C28") (pin "2") (pinfunction "2_2") (pintype "passive"))
      (node (ref "D1") (pin "1") (pinfunction "A_1") (pintype "passive"))
      (node (ref "H3") (pin "4") (pinfunction "4_4") (pintype "passive"))
      (node (ref "H7") (pin "3") (pinfunction "3_3") (pintype "passive"))
      (node (ref "L3") (pin "2") (pintype "passive"))
      (node (ref "U2") (pin "6") (pinfunction "VCCB_6") (pintype "passive"))
      (node (ref "U7") (pin "5") (pinfunction "FB_5") (pintype "input"))
    )
    (net (code "48") (name "GND") (class "Default")
      (node (ref "C1") (pin "1") (pinfunction "1_1") (pintype "passive"))
      (node (ref "C2") (pin "1") (pinfunction "1_1") (pintype "passive"))
      (node (ref "C23") (pin "1") (pinfunction "1_1") (pintype "passive"))
      (node (ref "C25") (pin "1") (pinfunction "1_1") (pintype "passive"))
      (node (ref "C27") (pin "1") (pinfunction "1_1") (pintype "passive"))
      (node (ref "C28") (pin "1") (pinfunction "1_1") (pintype "passive"))
      (node (ref "C29") (pin "1") (pinfunction "1_1") (pintype "passive"))
      (node (ref "C3") (pin "2") (pinfunction "2_2") (pintype "passive"))
      (node (ref "C30") (pin "2") (pinfunction "2_2") (pintype "passive"))
      (node (ref "C31") (pin "1") (pinfunction "1_1") (pintype "passive"))
      (node (ref "C32") (pin "2") (pinfunction "2_2") (pintype "passive"))
      (node (ref "C33") (pin "1") (pinfunction "1_1") (pintype "passive"))
      (node (ref "C34") (pin "2") (pinfunction "2_2") (pintype "passive"))
      (node (ref "C35") (pin "1") (pinfunction "1_1") (pintype "passive"))
      (node (ref "C36") (pin "2") (pinfunction "2_2") (pintype "passive"))
      (node (ref "C37") (pin "1") (pinfunction "1_1") (pintype "passive"))
      (node (ref "C38") (pin "1") (pinfunction "1_1") (pintype "passive"))
      (node (ref "C39") (pin "1") (pinfunction "1_1") (pintype "passive"))
      (node (ref "C4") (pin "1") (pinfunction "1_1") (pintype "passive"))
      (node (ref "C41") (pin "1") (pinfunction "1_1") (pintype "passive"))
      (node (ref "C42") (pin "1") (pinfunction "1_1") (pintype "passive"))
      (node (ref "C43") (pin "1") (pinfunction "1_1") (pintype "passive"))
      (node (ref "C44") (pin "1") (pinfunction "1_1") (pintype "passive"))
      (node (ref "D3") (pin "1") (pinfunction "A_1") (pintype "passive"))
      (node (ref "GND_TP_1") (pin "1") (pinfunction "1_1") (pintype "passive"))
      (node (ref "GND_TP_2") (pin "1") (pinfunction "1_1") (pintype "passive"))
      (node (ref "GND_TP_3") (pin "1") (pinfunction "1_1") (pintype "passive"))
      (node (ref "H1") (pin "10") (pinfunction "10_10") (pintype "passive"))
      (node (ref "H3") (pin "3") (pinfunction "3_3") (pintype "passive"))
      (node (ref "H5") (pin "1") (pinfunction "GND_1") (pintype "passive"))
      (node (ref "H5") (pin "3") (pinfunction "GND_3") (pintype "passive"))
      (node (ref "H6") (pin "10") (pinfunction "10_10") (pintype "passive"))
      (node (ref "H7") (pin "1") (pinfunction "1_1") (pintype "passive"))
      (node (ref "H8") (pin "5") (pinfunction "GND_5") (pintype "passive"))
      (node (ref "H8") (pin "6") (pinfunction "SHLD_6") (pintype "passive"))
      (node (ref "H9") (pin "5") (pinfunction "5_5") (pintype "passive"))
      (node (ref "H9") (pin "6") (pinfunction "6_6") (pintype "passive"))
      (node (ref "J1") (pin "1") (pinfunction "C1_1") (pintype "passive"))
      (node (ref "J2") (pin "1") (pinfunction "C1_1") (pintype "passive"))
      (node (ref "Q2") (pin "1") (pinfunction "1_1") (pintype "passive"))
      (node (ref "R18") (pin "1") (pinfunction "1_1") (pintype "passive"))
      (node (ref "R20") (pin "1") (pinfunction "1_1") (pintype "passive"))
      (node (ref "R5") (pin "1") (pinfunction "1_1") (pintype "passive"))
      (node (ref "R7") (pin "1") (pinfunction "1_1") (pintype "passive"))
      (node (ref "S3") (pin "2") (pintype "passive"))
      (node (ref "S4") (pin "2") (pintype "passive"))
      (node (ref "T1") (pin "2") (pinfunction "2_2") (pintype "passive"))
      (node (ref "U1") (pin "11") (pinfunction "FSYNC_11") (pintype "passive"))
      (node (ref "U1") (pin "18") (pinfunction "GND_18") (pintype "passive"))
      (node (ref "U1") (pin "20") (pinfunction "RESV_GND_20") (pintype "passive"))
      (node (ref "U1") (pin "9") (pinfunction "AD0/SDO_9") (pintype "passive"))
      (node (ref "U10") (pin "2") (pinfunction "GND_2") (pintype "power_in"))
      (node (ref "U2") (pin "2") (pinfunction "GND_2") (pintype "passive"))
      (node (ref "U6") (pin "17") (pinfunction "GND_17") (pintype "power_in"))
      (node (ref "U6") (pin "2") (pinfunction "GND_2") (pintype "power_in"))
      (node (ref "U6") (pin "46") (pinfunction "GND_46") (pintype "power_in"))
      (node (ref "U6") (pin "60") (pinfunction "GND_60") (pintype "power_in"))
      (node (ref "U7") (pin "7") (pinfunction "GND_7") (pintype "power_in"))
      (node (ref "U7") (pin "EPAD") (pinfunction "EPAD_EPAD") (pintype "passive"))
      (node (ref "U8") (pin "2") (pinfunction "GND_2") (pintype "passive"))
      (node (ref "U9") (pin "2") (pinfunction "GND_2") (pintype "power_in"))
      (node (ref "VR1") (pin "3") (pinfunction "3_3") (pintype "passive"))
      (node (ref "VR1") (pin "6") (pinfunction "3'_6") (pintype "passive"))
      (node (ref "VR1") (pin "8") (pinfunction "8_8") (pintype "passive"))
    )
    (net (code "49") (name "Net-(C40-Pad1)") (class "Default")
      (node (ref "C40") (pin "1") (pinfunction "1_1") (pintype "passive"))
      (node (ref "R18") (pin "2") (pinfunction "2_2") (pintype "passive"))
    )
    (net (code "50") (name "Net-(D1-K)") (class "Default")
      (node (ref "D1") (pin "2") (pinfunction "K_2") (pintype "passive"))
      (node (ref "D2") (pin "2") (pinfunction "K_2") (pintype "passive"))
      (node (ref "R10") (pin "1") (pinfunction "1_1") (pintype "passive"))
    )
    (net (code "51") (name "Net-(D3-K)") (class "Default")
      (node (ref "C26") (pin "2") (pinfunction "2_2") (pintype "passive"))
      (node (ref "D3") (pin "2") (pinfunction "K_2") (pintype "passive"))
      (node (ref "L3") (pin "1") (pintype "passive"))
      (node (ref "U7") (pin "8") (pinfunction "SW_8") (pintype "output"))
    )
    (net (code "52") (name "Net-(DL3-K)") (class "Default")
      (node (ref "DL3") (pin "1") (pinfunction "K_1") (pintype "passive"))
      (node (ref "R3") (pin "1") (pinfunction "1_1") (pintype "passive"))
    )
    (net (code "53") (name "Net-(DL4-K)") (class "Default")
      (node (ref "DL4") (pin "1") (pinfunction "K_1") (pintype "passive"))
      (node (ref "R4") (pin "1") (pinfunction "1_1") (pintype "passive"))
    )
    (net (code "54") (name "Net-(F2-Pad2)") (class "Default")
      (node (ref "F2") (pin "2") (pinfunction "2_2") (pintype "passive"))
      (node (ref "Q2") (pin "3") (pinfunction "3_3") (pintype "passive"))
      (node (ref "R8") (pin "1") (pinfunction "1_1") (pintype "passive"))
    )
    (net (code "55") (name "Net-(H2-Pad2)") (class "Default")
      (node (ref "H2") (pin "2") (pinfunction "2_2") (pintype "passive"))
      (node (ref "R17") (pin "1") (pinfunction "1_1") (pintype "passive"))
      (node (ref "T1") (pin "3") (pinfunction "3_3") (pintype "passive"))
    )
    (net (code "56") (name "Net-(H5-VBATT)") (class "Default")
      (node (ref "F2") (pin "1") (pinfunction "1_1") (pintype "passive"))
      (node (ref "H5") (pin "2") (pinfunction "VBATT_2") (pintype "passive"))
    )
    (net (code "57") (name "Net-(J1-C2)") (class "Default")
      (node (ref "J1") (pin "2") (pinfunction "C2_2") (pintype "passive"))
      (node (ref "U6") (pin "5") (pinfunction "PB2/AD6_5") (pintype "bidirectional"))
    )
    (net (code "58") (name "Net-(J2-C2)") (class "Default")
      (node (ref "J2") (pin "2") (pinfunction "C2_2") (pintype "passive"))
      (node (ref "U6") (pin "4") (pinfunction "PB1/AD5_4") (pintype "bidirectional"))
    )
    (net (code "59") (name "Net-(Q2-Pad2)") (class "Default")
      (node (ref "Q2") (pin "2") (pinfunction "2_2") (pintype "passive"))
      (node (ref "R9") (pin "1") (pinfunction "1_1") (pintype "passive"))
    )
    (net (code "60") (name "Net-(U1-REGOUT)") (class "Default")
      (node (ref "C3") (pin "1") (pinfunction "1_1") (pintype "passive"))
      (node (ref "U1") (pin "10") (pinfunction "REGOUT_10") (pintype "passive"))
    )
    (net (code "61") (name "Net-(U6A-ERASE{slash}PB12)") (class "Default")
      (node (ref "RST") (pin "1") (pinfunction "1_1") (pintype "passive"))
      (node (ref "U6") (pin "55") (pinfunction "ERASE/PB12_55") (pintype "bidirectional"))
    )
    (net (code "62") (name "Net-(U6A-XIN{slash}PGMCK{slash}PB9)") (class "Default")
      (node (ref "C23") (pin "2") (pinfunction "2_2") (pintype "passive"))
      (node (ref "U6") (pin "62") (pinfunction "XIN/PGMCK/PB9_62") (pintype "bidirectional"))
      (node (ref "Y2") (pin "1") (pinfunction "OSC1_1") (pintype "passive"))
    )
    (net (code "63") (name "Net-(U6A-XOUT{slash}PB8)") (class "Default")
      (node (ref "C25") (pin "2") (pinfunction "2_2") (pintype "passive"))
      (node (ref "U6") (pin "61") (pinfunction "XOUT/PB8_61") (pintype "bidirectional"))
      (node (ref "Y2") (pin "3") (pinfunction "OSC2_3") (pintype "passive"))
    )
    (net (code "64") (name "Net-(U6B-VDDOUT)") (class "Default")
      (node (ref "C30") (pin "1") (pinfunction "1_1") (pintype "passive"))
      (node (ref "C32") (pin "1") (pinfunction "1_1") (pintype "passive"))
      (node (ref "C34") (pin "1") (pinfunction "1_1") (pintype "passive"))
      (node (ref "C36") (pin "1") (pinfunction "1_1") (pintype "passive"))
      (node (ref "L4") (pin "2") (pinfunction "2_2") (pintype "passive"))
      (node (ref "U6") (pin "12") (pinfunction "VDDCORE_12") (pintype "power_in"))
      (node (ref "U6") (pin "24") (pinfunction "VDDCORE_24") (pintype "power_in"))
      (node (ref "U6") (pin "54") (pinfunction "VDDCORE_54") (pintype "power_in"))
      (node (ref "U6") (pin "8") (pinfunction "VDDOUT_8") (pintype "power_in"))
    )
    (net (code "65") (name "Net-(U6B-VDDPLL)") (class "Default")
      (node (ref "C39") (pin "2") (pinfunction "2_2") (pintype "passive"))
      (node (ref "C40") (pin "2") (pinfunction "2_2") (pintype "passive"))
      (node (ref "L4") (pin "1") (pinfunction "1_1") (pintype "passive"))
      (node (ref "U6") (pin "64") (pinfunction "VDDPLL_64") (pintype "power_in"))
    )
    (net (code "66") (name "Net-(U7-BST)") (class "Default")
      (node (ref "C26") (pin "1") (pinfunction "1_1") (pintype "passive"))
      (node (ref "U7") (pin "1") (pinfunction "BST_1") (pintype "passive"))
    )
    (net (code "67") (name "Net-(U7-PGOOD)") (class "Default")
      (node (ref "R14") (pin "1") (pinfunction "1_1") (pintype "passive"))
      (node (ref "U7") (pin "4") (pinfunction "PGOOD_4") (pintype "output"))
    )
    (net (code "68") (name "Net-(U8-VCC)") (class "Default")
      (node (ref "C38") (pin "2") (pinfunction "2_2") (pintype "passive"))
      (node (ref "R15") (pin "2") (pinfunction "2_2") (pintype "passive"))
      (node (ref "U8") (pin "1") (pinfunction "VCC_1") (pintype "passive"))
    )
    (net (code "69") (name "Net-(U9-OUT)") (class "Default")
      (node (ref "C42") (pin "2") (pinfunction "2_2") (pintype "passive"))
      (node (ref "R11") (pin "1") (pinfunction "1_1") (pintype "passive"))
      (node (ref "U9") (pin "5") (pinfunction "OUT_5") (pintype "power_in"))
    )
    (net (code "70") (name "Net-(U10-OUT)") (class "Default")
      (node (ref "C44") (pin "2") (pinfunction "2_2") (pintype "passive"))
      (node (ref "R16") (pin "1") (pinfunction "1_1") (pintype "passive"))
      (node (ref "U10") (pin "5") (pinfunction "OUT_5") (pintype "power_in"))
    )
    (net (code "71") (name "USB_DETECT") (class "Default")
      (node (ref "R19") (pin "1") (pinfunction "1_1") (pintype "passive"))
      (node (ref "R20") (pin "2") (pinfunction "2_2") (pintype "passive"))
      (node (ref "U6") (pin "35") (pinfunction "PA5/PGMRDY_35") (pintype "bidirectional"))
      (node (ref "USB_DETECT_TP1") (pin "1") (pinfunction "1_1") (pintype "passive"))
    )
    (net (code "72") (name "VBUS") (class "Default")
      (node (ref "D2") (pin "1") (pinfunction "A_1") (pintype "passive"))
      (node (ref "H8") (pin "1") (pinfunction "VBUS_1") (pintype "power_in"))
      (node (ref "R19") (pin "2") (pinfunction "2_2") (pintype "passive"))
      (node (ref "R8") (pin "2") (pinfunction "2_2") (pintype "passive"))
      (node (ref "VBUS_TP1") (pin "1") (pinfunction "1_1") (pintype "passive"))
    )
    (net (code "73") (name "V_BAT") (class "Default")
      (node (ref "C4") (pin "2") (pinfunction "2_2") (pintype "passive"))
      (node (ref "H3") (pin "5") (pinfunction "5_5") (pintype "passive"))
      (node (ref "R14") (pin "2") (pinfunction "2_2") (pintype "passive"))
      (node (ref "R6") (pin "2") (pinfunction "2_2") (pintype "passive"))
      (node (ref "R9") (pin "2") (pinfunction "2_2") (pintype "passive"))
      (node (ref "U7") (pin "2") (pinfunction "VIN_2") (pintype "input"))
      (node (ref "U7") (pin "3") (pinfunction "EN_3") (pintype "output"))
      (node (ref "V_BATT_TP1") (pin "1") (pinfunction "1_1") (pintype "passive"))
    )
    (net (code "74") (name "unconnected-(H8-ID-Pad4)") (class "Default")
      (node (ref "H8") (pin "4") (pinfunction "ID_4") (pintype "power_in"))
    )
    (net (code "75") (name "unconnected-(H9-Pad3)") (class "Default")
      (node (ref "H9") (pin "3") (pinfunction "3_3") (pintype "passive+no_connect"))
    )
    (net (code "76") (name "unconnected-(H9-Pad9)") (class "Default")
      (node (ref "H9") (pin "9") (pinfunction "9_9") (pintype "passive+no_connect"))
    )
    (net (code "77") (name "unconnected-(H9-Pad10)") (class "Default")
      (node (ref "H9") (pin "10") (pinfunction "10_10") (pintype "passive+no_connect"))
    )
    (net (code "78") (name "unconnected-(U1-AUX_CL-Pad7)") (class "Default")
      (node (ref "U1") (pin "7") (pinfunction "AUX_CL_7") (pintype "passive+no_connect"))
    )
    (net (code "79") (name "unconnected-(U1-AUX_DA-Pad21)") (class "Default")
      (node (ref "U1") (pin "21") (pinfunction "AUX_DA_21") (pintype "passive+no_connect"))
    )
    (net (code "80") (name "unconnected-(U1-INT-Pad12)") (class "Default")
      (node (ref "U1") (pin "12") (pinfunction "INT_12") (pintype "passive+no_connect"))
    )
    (net (code "81") (name "unconnected-(U6A-JTAGSEL-Pad50)") (class "Default")
      (node (ref "U6") (pin "50") (pinfunction "JTAGSEL_50") (pintype "input+no_connect"))
    )
    (net (code "82") (name "unconnected-(U6A-TDI{slash}PB4-Pad33)") (class "Default")
      (node (ref "U6") (pin "33") (pinfunction "TDI/PB4_33") (pintype "bidirectional+no_connect"))
    )
    (net (code "83") (name "unconnected-(U6A-TDO{slash}TRACESWO{slash}PB5-Pad49)") (class "Default")
      (node (ref "U6") (pin "49") (pinfunction "TDO/TRACESWO/PB5_49") (pintype "bidirectional+no_connect"))
    )
    (net (code "84") (name "unconnected-(U6A-TST-Pad40)") (class "Default")
      (node (ref "U6") (pin "40") (pinfunction "TST_40") (pintype "input+no_connect"))
    )
    (net (code "85") (name "unconnected-(U7-NC-Pad6)") (class "Default")
      (node (ref "U7") (pin "6") (pinfunction "NC_6") (pintype "passive+no_connect"))
    )
    (net (code "86") (name "unconnected-(U9-BYP-Pad4)") (class "Default")
      (node (ref "U9") (pin "4") (pinfunction "BYP_4") (pintype "passive"))
    )
    (net (code "87") (name "unconnected-(U10-BYP-Pad4)") (class "Default")
      (node (ref "U10") (pin "4") (pinfunction "BYP_4") (pintype "passive"))
    )
    (net (code "88") (name "unconnected-(VR1-Pad9)") (class "Default")
      (node (ref "VR1") (pin "9") (pinfunction "9_9") (pintype "passive+no_connect"))
    )
    (net (code "89") (name "unconnected-(VR1-Pad10)") (class "Default")
      (node (ref "VR1") (pin "10") (pinfunction "10_10") (pintype "passive+no_connect"))
    )
  )
)
